# usbkey.net
KiCad netlist of a schematic drawn in EAGLE
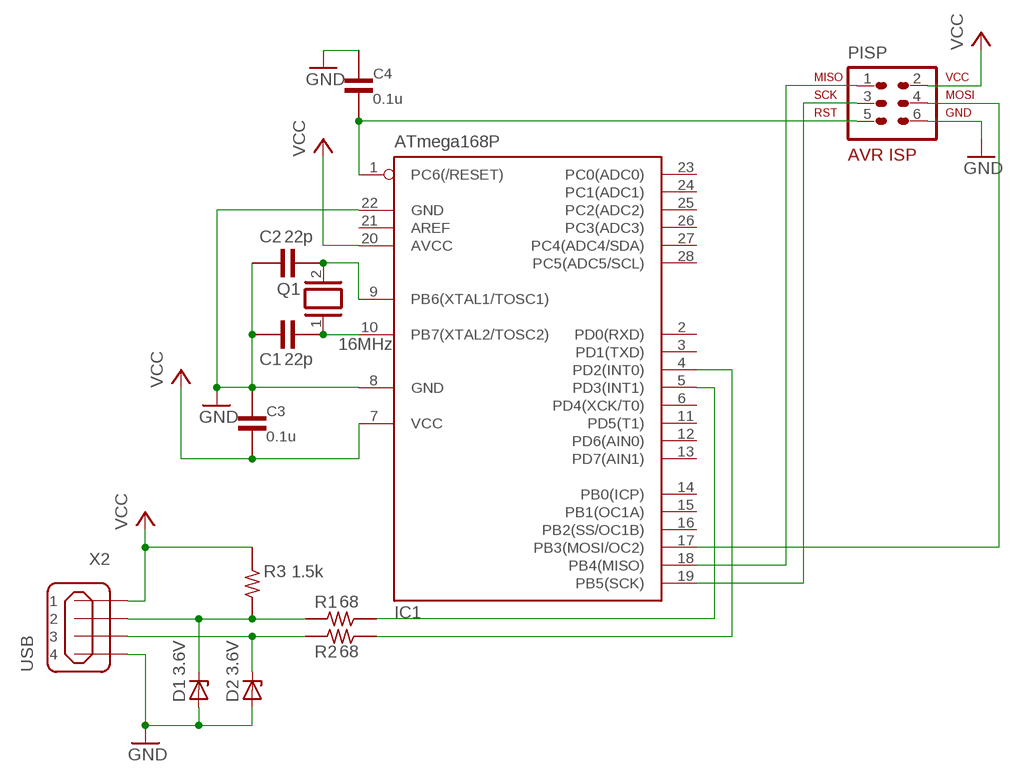
[diagram p0: schematic, sheet 1]

(export (version "E")
  (design (tool "Eeschema 10.0.6"))
  (components
    (comp (ref "C1")
      (value "22p")
      (footprint "eagle-import:50-0302-2.54")
      (libsource (lib "eagle-import") (part "C-50V-0302-2.54"))
    )
    (comp (ref "C2")
      (value "22p")
      (footprint "eagle-import:50-0302-2.54")
      (libsource (lib "eagle-import") (part "C-50V-0302-2.54"))
    )
    (comp (ref "C3")
      (value "0.1u")
      (footprint "eagle-import:50-0302-2.54")
      (libsource (lib "eagle-import") (part "C-50V-0302-2.54"))
    )
    (comp (ref "C4")
      (value "0.1u")
      (footprint "eagle-import:50-0302-2.54")
      (libsource (lib "eagle-import") (part "C-50V-0302-2.54"))
    )
    (comp (ref "D1")
      (value "3.6V")
      (footprint "eagle-import:DO35Z10")
      (libsource (lib "eagle-import") (part "BZX55"))
    )
    (comp (ref "D2")
      (value "3.6V")
      (footprint "eagle-import:DO35Z10")
      (libsource (lib "eagle-import") (part "BZX55"))
    )
    (comp (ref "IC1")
      (value "ATmega168P")
      (footprint "eagle-import:DIL28-3")
      (libsource (lib "eagle-import") (part "MEGA8-P"))
    )
    (comp (ref "PISP")
      (value "AVR-ISP-6VERT")
      (footprint "eagle-import:AVR-ISP-6")
      (libsource (lib "eagle-import") (part "AVR-ISP-6VERT"))
    )
    (comp (ref "Q1")
      (value "16MHz")
      (footprint "eagle-import:QS")
      (libsource (lib "eagle-import") (part "XTAL/S"))
    )
    (comp (ref "R1")
      (value "68")
      (footprint "eagle-import:1_4W-7.62H")
      (libsource (lib "eagle-import") (part "R-1/4W-07.62"))
    )
    (comp (ref "R2")
      (value "68")
      (footprint "eagle-import:1_4W-7.62H")
      (libsource (lib "eagle-import") (part "R-1/4W-07.62"))
    )
    (comp (ref "R3")
      (value "1.5k")
      (footprint "eagle-import:1_4W-2.54V")
      (libsource (lib "eagle-import") (part "R-1/4W-02.54-V"))
    )
    (comp (ref "X2")
      (value "USB")
      (footprint "eagle-import:85-32004-10X")
      (libsource (lib "eagle-import") (part "MINI-USB_SHIELD4P-85-32004-10X"))
    )
  )
  (nets
    (net (code "1") (name "GND") (class "Default")
      (node (ref "C1") (pin "PAD2") (pinfunction "2_PAD2") (pintype "passive"))
      (node (ref "C2") (pin "PAD2") (pinfunction "2_PAD2") (pintype "passive"))
      (node (ref "C3") (pin "PAD1") (pinfunction "1_PAD1") (pintype "passive"))
      (node (ref "C4") (pin "PAD1") (pinfunction "1_PAD1") (pintype "passive"))
      (node (ref "D1") (pin "A") (pinfunction "A_A") (pintype "passive"))
      (node (ref "D2") (pin "A") (pinfunction "A_A") (pintype "passive"))
      (node (ref "IC1") (pin "22") (pinfunction "GND_22") (pintype "power_in"))
      (node (ref "IC1") (pin "8") (pinfunction "GND_8") (pintype "power_in"))
      (node (ref "PISP") (pin "6") (pinfunction "6_6") (pintype "passive"))
      (node (ref "X2") (pin "4") (pinfunction "4_4") (pintype "passive"))
    )
    (net (code "2") (name "Net-(C1-1)") (class "Default")
      (node (ref "C1") (pin "PAD1") (pinfunction "1_PAD1") (pintype "passive"))
      (node (ref "IC1") (pin "10") (pinfunction "PB7(XTAL2/TOSC2)_10") (pintype "bidirectional"))
      (node (ref "Q1") (pin "1") (pinfunction "1_1") (pintype "passive"))
    )
    (net (code "3") (name "Net-(C2-1)") (class "Default")
      (node (ref "C2") (pin "PAD1") (pinfunction "1_PAD1") (pintype "passive"))
      (node (ref "IC1") (pin "9") (pinfunction "PB6(XTAL1/TOSC1)_9") (pintype "bidirectional"))
      (node (ref "Q1") (pin "2") (pinfunction "2_2") (pintype "passive"))
    )
    (net (code "4") (name "Net-(C4-2)") (class "Default")
      (node (ref "C4") (pin "PAD2") (pinfunction "2_PAD2") (pintype "passive"))
      (node (ref "IC1") (pin "1") (pinfunction "PC6(/RESET)_1") (pintype "bidirectional"))
      (node (ref "PISP") (pin "5") (pinfunction "5_5") (pintype "passive"))
    )
    (net (code "5") (name "Net-(IC1-PB3(MOSI{slash}OC2))") (class "Default")
      (node (ref "IC1") (pin "17") (pinfunction "PB3(MOSI/OC2)_17") (pintype "bidirectional"))
      (node (ref "PISP") (pin "4") (pinfunction "4_4") (pintype "passive"))
    )
    (net (code "6") (name "Net-(IC1-PB4(MISO))") (class "Default")
      (node (ref "IC1") (pin "18") (pinfunction "PB4(MISO)_18") (pintype "bidirectional"))
      (node (ref "PISP") (pin "1") (pinfunction "1_1") (pintype "passive"))
    )
    (net (code "7") (name "Net-(IC1-PB5(SCK))") (class "Default")
      (node (ref "IC1") (pin "19") (pinfunction "PB5(SCK)_19") (pintype "bidirectional"))
      (node (ref "PISP") (pin "3") (pinfunction "3_3") (pintype "passive"))
    )
    (net (code "8") (name "Net-(IC1-PD2(INT0))") (class "Default")
      (node (ref "IC1") (pin "4") (pinfunction "PD2(INT0)_4") (pintype "bidirectional"))
      (node (ref "R2") (pin "PAD2") (pinfunction "2_PAD2") (pintype "passive"))
    )
    (net (code "9") (name "Net-(IC1-PD3(INT1))") (class "Default")
      (node (ref "IC1") (pin "5") (pinfunction "PD3(INT1)_5") (pintype "bidirectional"))
      (node (ref "R1") (pin "PAD2") (pinfunction "2_PAD2") (pintype "passive"))
    )
    (net (code "10") (name "Net-(R1-1)") (class "Default")
      (node (ref "D1") (pin "C") (pinfunction "C_C") (pintype "passive"))
      (node (ref "R1") (pin "PAD1") (pinfunction "1_PAD1") (pintype "passive"))
      (node (ref "R3") (pin "PAD1") (pinfunction "1_PAD1") (pintype "passive"))
      (node (ref "X2") (pin "2") (pinfunction "2_2") (pintype "passive"))
    )
    (net (code "11") (name "Net-(R2-1)") (class "Default")
      (node (ref "D2") (pin "C") (pinfunction "C_C") (pintype "passive"))
      (node (ref "R2") (pin "PAD1") (pinfunction "1_PAD1") (pintype "passive"))
      (node (ref "X2") (pin "3") (pinfunction "3_3") (pintype "passive"))
    )
    (net (code "12") (name "VCC") (class "Default")
      (node (ref "C3") (pin "PAD2") (pinfunction "2_PAD2") (pintype "passive"))
      (node (ref "IC1") (pin "20") (pinfunction "AVCC_20") (pintype "power_in"))
      (node (ref "IC1") (pin "7") (pinfunction "VCC_7") (pintype "power_in"))
      (node (ref "PISP") (pin "2") (pinfunction "2_2") (pintype "passive"))
      (node (ref "R3") (pin "PAD2") (pinfunction "2_PAD2") (pintype "passive"))
      (node (ref "X2") (pin "1") (pinfunction "1_1") (pintype "passive"))
    )
    (net (code "13") (name "unconnected-(IC1-AREF-Pad21)") (class "Default")
      (node (ref "IC1") (pin "21") (pinfunction "AREF_21") (pintype "passive"))
    )
    (net (code "14") (name "unconnected-(IC1-PB0(ICP)-Pad14)") (class "Default")
      (node (ref "IC1") (pin "14") (pinfunction "PB0(ICP)_14") (pintype "bidirectional"))
    )
    (net (code "15") (name "unconnected-(IC1-PB1(OC1A)-Pad15)") (class "Default")
      (node (ref "IC1") (pin "15") (pinfunction "PB1(OC1A)_15") (pintype "bidirectional"))
    )
    (net (code "16") (name "unconnected-(IC1-PB2(SS{slash}OC1B)-Pad16)") (class "Default")
      (node (ref "IC1") (pin "16") (pinfunction "PB2(SS/OC1B)_16") (pintype "bidirectional"))
    )
    (net (code "17") (name "unconnected-(IC1-PC0(ADC0)-Pad23)") (class "Default")
      (node (ref "IC1") (pin "23") (pinfunction "PC0(ADC0)_23") (pintype "bidirectional"))
    )
    (net (code "18") (name "unconnected-(IC1-PC1(ADC1)-Pad24)") (class "Default")
      (node (ref "IC1") (pin "24") (pinfunction "PC1(ADC1)_24") (pintype "bidirectional"))
    )
    (net (code "19") (name "unconnected-(IC1-PC2(ADC2)-Pad25)") (class "Default")
      (node (ref "IC1") (pin "25") (pinfunction "PC2(ADC2)_25") (pintype "bidirectional"))
    )
    (net (code "20") (name "unconnected-(IC1-PC3(ADC3)-Pad26)") (class "Default")
      (node (ref "IC1") (pin "26") (pinfunction "PC3(ADC3)_26") (pintype "bidirectional"))
    )
    (net (code "21") (name "unconnected-(IC1-PC4(ADC4{slash}SDA)-Pad27)") (class "Default")
      (node (ref "IC1") (pin "27") (pinfunction "PC4(ADC4/SDA)_27") (pintype "bidirectional"))
    )
    (net (code "22") (name "unconnected-(IC1-PC5(ADC5{slash}SCL)-Pad28)") (class "Default")
      (node (ref "IC1") (pin "28") (pinfunction "PC5(ADC5/SCL)_28") (pintype "bidirectional"))
    )
    (net (code "23") (name "unconnected-(IC1-PD0(RXD)-Pad2)") (class "Default")
      (node (ref "IC1") (pin "2") (pinfunction "PD0(RXD)_2") (pintype "bidirectional"))
    )
    (net (code "24") (name "unconnected-(IC1-PD1(TXD)-Pad3)") (class "Default")
      (node (ref "IC1") (pin "3") (pinfunction "PD1(TXD)_3") (pintype "bidirectional"))
    )
    (net (code "25") (name "unconnected-(IC1-PD4(XCK{slash}T0)-Pad6)") (class "Default")
      (node (ref "IC1") (pin "6") (pinfunction "PD4(XCK/T0)_6") (pintype "bidirectional"))
    )
    (net (code "26") (name "unconnected-(IC1-PD5(T1)-Pad11)") (class "Default")
      (node (ref "IC1") (pin "11") (pinfunction "PD5(T1)_11") (pintype "bidirectional"))
    )
    (net (code "27") (name "unconnected-(IC1-PD6(AIN0)-Pad12)") (class "Default")
      (node (ref "IC1") (pin "12") (pinfunction "PD6(AIN0)_12") (pintype "bidirectional"))
    )
    (net (code "28") (name "unconnected-(IC1-PD7(AIN1)-Pad13)") (class "Default")
      (node (ref "IC1") (pin "13") (pinfunction "PD7(AIN1)_13") (pintype "bidirectional"))
    )
  )
)
